# 24V_to_5V_GSM_regulator.net
KiCad netlist of a schematic drawn in Altium Designer
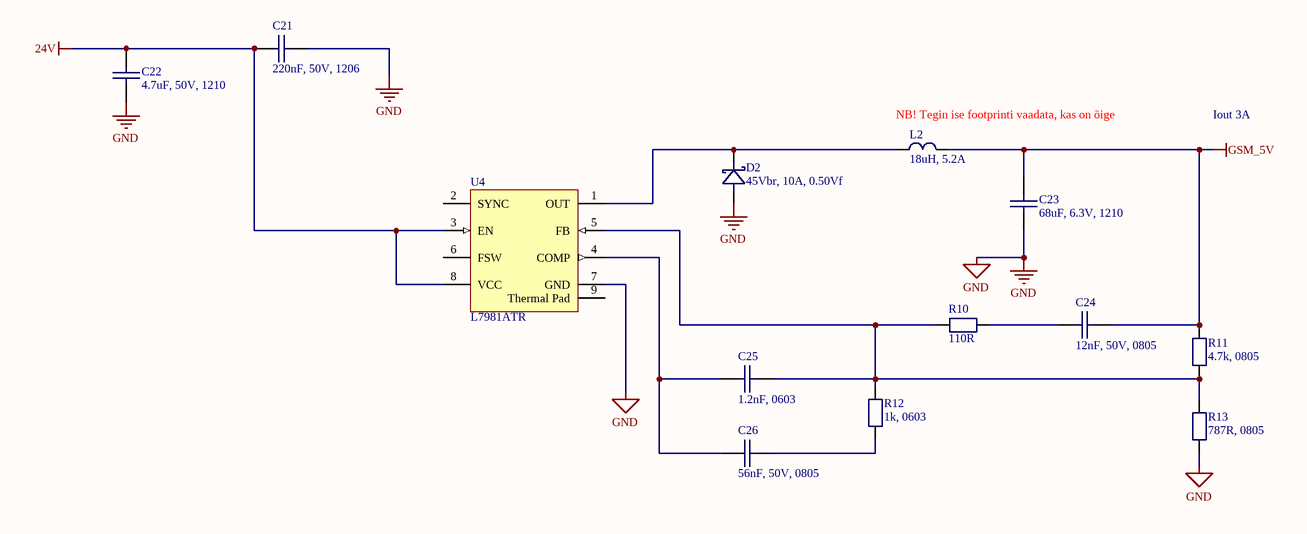
[diagram p0: 24V_to_5V_GSM_regulator.SchDoc]

(export (version "E")
  (design (tool "Eeschema 10.0.6"))
  (components
    (comp (ref "C21")
      (value "220nF, 50V, 1206")
      (footprint "3216 [1206] CAP")
      (libsource (lib "AS_component_library") (part "Capacitor"))
    )
    (comp (ref "C22")
      (value "4.7uF, 50V, 1210")
      (footprint "3225 [1210] CAP")
      (libsource (lib "AS_component_library") (part "Capacitor"))
    )
    (comp (ref "C23")
      (value "68uF, 6.3V, 1210")
      (footprint "3225 [1210] CAP")
      (libsource (lib "AS_component_library") (part "Capacitor"))
    )
    (comp (ref "C24")
      (value "12nF, 50V, 0805")
      (footprint "2012 [0805] CAP")
      (libsource (lib "AS_component_library") (part "Capacitor"))
    )
    (comp (ref "C25")
      (value "1.2nF, 0603")
      (footprint "1608 [0603] CAP")
      (libsource (lib "AS_component_library") (part "Capacitor"))
    )
    (comp (ref "C26")
      (value "56nF, 50V, 0805")
      (footprint "2012 [0805] CAP")
      (libsource (lib "AS_component_library") (part "Capacitor"))
    )
    (comp (ref "D2")
      (value "45Vbr, 10A, 0.50Vf")
      (footprint "DPAK (TO252-3)")
      (libsource (lib "AS_component_library") (part "Diode Shottky"))
    )
    (comp (ref "L2")
      (value "18uH, 5.2A")
      (footprint "12.5 x 12.5 x 8.5 (mm)")
      (libsource (lib "AS_component_library") (part "Inductor"))
    )
    (comp (ref "R10")
      (value "110R")
      (footprint "2012 [0805] RES")
      (libsource (lib "AS_component_library") (part "Resistor"))
    )
    (comp (ref "R11")
      (value "4.7k, 0805")
      (footprint "2012 [0805] RES")
      (libsource (lib "AS_component_library") (part "Resistor"))
    )
    (comp (ref "R12")
      (value "1k, 0603")
      (footprint "1608 [0603] RES")
      (libsource (lib "AS_component_library") (part "Resistor"))
    )
    (comp (ref "R13")
      (value "787R, 0805")
      (footprint "2012 [0805] RES")
      (libsource (lib "AS_component_library") (part "Resistor"))
    )
    (comp (ref "U4")
      (value "L7981ATR")
      (footprint "HSOP8-D1_N")
      (description "3 A step-down switching regulator, 8-Pin HSOP, Tape and Reel")
      (libsource (lib "STMicroelectronics Power Management DC-DC Conversion") (part "L7981ATR"))
    )
  )
  (nets
    (net (code "1") (name "24V") (class "Default")
      (node (ref "C21") (pin "2") (pinfunction "2_2") (pintype "passive"))
      (node (ref "C22") (pin "1") (pinfunction "1_1") (pintype "passive"))
      (node (ref "U4") (pin "3") (pinfunction "EN_3") (pintype "input"))
      (node (ref "U4") (pin "8") (pinfunction "VCC_8") (pintype "power_in"))
    )
    (net (code "2") (name "GND") (class "Default")
      (node (ref "C21") (pin "1") (pinfunction "1_1") (pintype "passive"))
      (node (ref "C22") (pin "2") (pinfunction "2_2") (pintype "passive"))
      (node (ref "C23") (pin "2") (pinfunction "2_2") (pintype "passive"))
      (node (ref "D2") (pin "2") (pinfunction "2_2") (pintype "passive"))
      (node (ref "R13") (pin "1") (pinfunction "1_1") (pintype "passive"))
      (node (ref "U4") (pin "7") (pinfunction "GND_7") (pintype "power_in"))
    )
    (net (code "3") (name "GSM_5V") (class "Default")
      (node (ref "C23") (pin "1") (pinfunction "1_1") (pintype "passive"))
      (node (ref "C24") (pin "1") (pinfunction "1_1") (pintype "passive"))
      (node (ref "L2") (pin "2") (pinfunction "2_2") (pintype "passive"))
      (node (ref "R11") (pin "2") (pinfunction "2_2") (pintype "passive"))
    )
    (net (code "4") (name "Net-(C24-Pad2)") (class "Default")
      (node (ref "C24") (pin "2") (pinfunction "2_2") (pintype "passive"))
      (node (ref "R10") (pin "2") (pinfunction "2_2") (pintype "passive"))
    )
    (net (code "5") (name "Net-(C26-Pad1)") (class "Default")
      (node (ref "C26") (pin "1") (pinfunction "1_1") (pintype "passive"))
      (node (ref "R12") (pin "1") (pinfunction "1_1") (pintype "passive"))
    )
    (net (code "6") (name "Net-(U4-COMP)") (class "Default")
      (node (ref "C25") (pin "2") (pinfunction "2_2") (pintype "passive"))
      (node (ref "C26") (pin "2") (pinfunction "2_2") (pintype "passive"))
      (node (ref "U4") (pin "4") (pinfunction "COMP_4") (pintype "output"))
    )
    (net (code "7") (name "Net-(U4-FB)") (class "Default")
      (node (ref "C25") (pin "1") (pinfunction "1_1") (pintype "passive"))
      (node (ref "R10") (pin "1") (pinfunction "1_1") (pintype "passive"))
      (node (ref "R11") (pin "1") (pinfunction "1_1") (pintype "passive"))
      (node (ref "R12") (pin "2") (pinfunction "2_2") (pintype "passive"))
      (node (ref "R13") (pin "2") (pinfunction "2_2") (pintype "passive"))
      (node (ref "U4") (pin "5") (pinfunction "FB_5") (pintype "input"))
    )
    (net (code "8") (name "Net-(U4-OUT)") (class "Default")
      (node (ref "D2") (pin "1") (pinfunction "1_1") (pintype "passive"))
      (node (ref "L2") (pin "1") (pinfunction "1_1") (pintype "passive"))
      (node (ref "U4") (pin "1") (pinfunction "OUT_1") (pintype "power_in"))
    )
    (net (code "9") (name "unconnected-(U4-FSW-Pad6)") (class "Default")
      (node (ref "U4") (pin "6") (pinfunction "FSW_6") (pintype "passive"))
    )
    (net (code "10") (name "unconnected-(U4-SYNC-Pad2)") (class "Default")
      (node (ref "U4") (pin "2") (pinfunction "SYNC_2") (pintype "passive"))
    )
    (net (code "11") (name "unconnected-(U4-Thermal_Pad-Pad9)") (class "Default")
      (node (ref "U4") (pin "9") (pinfunction "Thermal_Pad_9") (pintype "power_in"))
    )
  )
)
